# NP_5x5_2020.net
KiCad netlist of a schematic drawn in EAGLE
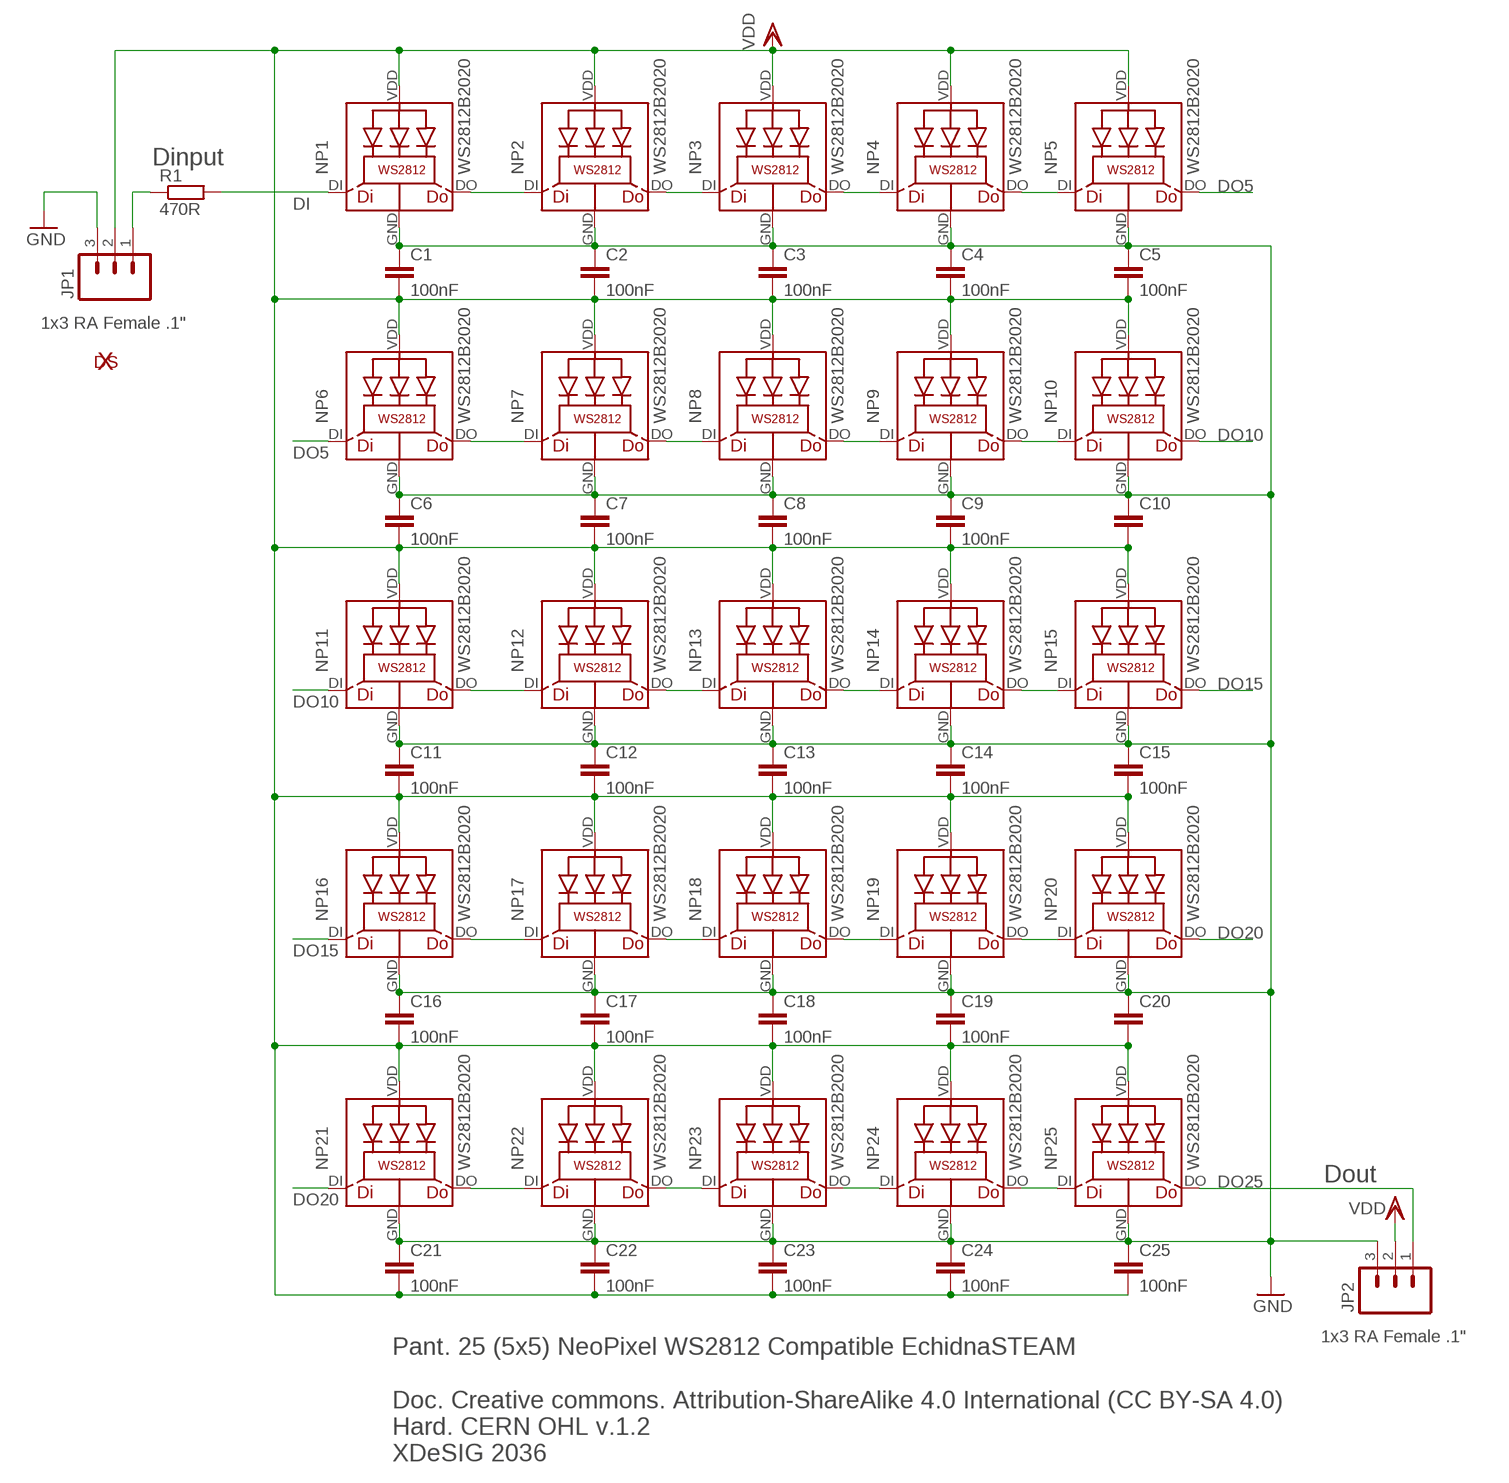
[diagram p0: schematic, sheet 1]

(export (version "E")
  (design (tool "Eeschema 10.0.6"))
  (components
    (comp (ref "C1")
      (value "100nF")
      (footprint "eagle-import:C0402")
      (libsource (lib "eagle-import") (part "C-EUC0402"))
    )
    (comp (ref "C2")
      (value "100nF")
      (footprint "eagle-import:C0402")
      (libsource (lib "eagle-import") (part "C-EUC0402"))
    )
    (comp (ref "C3")
      (value "100nF")
      (footprint "eagle-import:C0402")
      (libsource (lib "eagle-import") (part "C-EUC0402"))
    )
    (comp (ref "C4")
      (value "100nF")
      (footprint "eagle-import:C0402")
      (libsource (lib "eagle-import") (part "C-EUC0402"))
    )
    (comp (ref "C5")
      (value "100nF")
      (footprint "eagle-import:C0402")
      (libsource (lib "eagle-import") (part "C-EUC0402"))
    )
    (comp (ref "C6")
      (value "100nF")
      (footprint "eagle-import:C0402")
      (libsource (lib "eagle-import") (part "C-EUC0402"))
    )
    (comp (ref "C7")
      (value "100nF")
      (footprint "eagle-import:C0402")
      (libsource (lib "eagle-import") (part "C-EUC0402"))
    )
    (comp (ref "C8")
      (value "100nF")
      (footprint "eagle-import:C0402")
      (libsource (lib "eagle-import") (part "C-EUC0402"))
    )
    (comp (ref "C9")
      (value "100nF")
      (footprint "eagle-import:C0402")
      (libsource (lib "eagle-import") (part "C-EUC0402"))
    )
    (comp (ref "C10")
      (value "C-EUC0402")
      (footprint "eagle-import:C0402")
      (libsource (lib "eagle-import") (part "C-EUC0402"))
    )
    (comp (ref "C11")
      (value "100nF")
      (footprint "eagle-import:C0402")
      (libsource (lib "eagle-import") (part "C-EUC0402"))
    )
    (comp (ref "C12")
      (value "100nF")
      (footprint "eagle-import:C0402")
      (libsource (lib "eagle-import") (part "C-EUC0402"))
    )
    (comp (ref "C13")
      (value "100nF")
      (footprint "eagle-import:C0402")
      (libsource (lib "eagle-import") (part "C-EUC0402"))
    )
    (comp (ref "C14")
      (value "100nF")
      (footprint "eagle-import:C0402")
      (libsource (lib "eagle-import") (part "C-EUC0402"))
    )
    (comp (ref "C15")
      (value "100nF")
      (footprint "eagle-import:C0402")
      (libsource (lib "eagle-import") (part "C-EUC0402"))
    )
    (comp (ref "C16")
      (value "100nF")
      (footprint "eagle-import:C0402")
      (libsource (lib "eagle-import") (part "C-EUC0402"))
    )
    (comp (ref "C17")
      (value "100nF")
      (footprint "eagle-import:C0402")
      (libsource (lib "eagle-import") (part "C-EUC0402"))
    )
    (comp (ref "C18")
      (value "100nF")
      (footprint "eagle-import:C0402")
      (libsource (lib "eagle-import") (part "C-EUC0402"))
    )
    (comp (ref "C19")
      (value "100nF")
      (footprint "eagle-import:C0402")
      (libsource (lib "eagle-import") (part "C-EUC0402"))
    )
    (comp (ref "C20")
      (value "C-EUC0402")
      (footprint "eagle-import:C0402")
      (libsource (lib "eagle-import") (part "C-EUC0402"))
    )
    (comp (ref "C21")
      (value "100nF")
      (footprint "eagle-import:C0402")
      (libsource (lib "eagle-import") (part "C-EUC0402"))
    )
    (comp (ref "C22")
      (value "100nF")
      (footprint "eagle-import:C0402")
      (libsource (lib "eagle-import") (part "C-EUC0402"))
    )
    (comp (ref "C23")
      (value "100nF")
      (footprint "eagle-import:C0402")
      (libsource (lib "eagle-import") (part "C-EUC0402"))
    )
    (comp (ref "C24")
      (value "100nF")
      (footprint "eagle-import:C0402")
      (libsource (lib "eagle-import") (part "C-EUC0402"))
    )
    (comp (ref "C25")
      (value "100nF")
      (footprint "eagle-import:C0402")
      (libsource (lib "eagle-import") (part "C-EUC0402"))
    )
    (comp (ref "JP1")
      (value "1x3 RA Female .1\"")
      (footprint "eagle-import:1X03_SMD_RA_FEMALE")
      (libsource (lib "eagle-import") (part "M03SMD_RA_FEMALE"))
    )
    (comp (ref "JP2")
      (value "1x3 RA Female .1\"")
      (footprint "eagle-import:1X03_SMD_RA_FEMALE")
      (libsource (lib "eagle-import") (part "M03SMD_RA_FEMALE"))
    )
    (comp (ref "NP1")
      (value "WS2812B2020")
      (footprint "eagle-import:2020")
      (libsource (lib "eagle-import") (part "WS2812B2020"))
    )
    (comp (ref "NP2")
      (value "WS2812B2020")
      (footprint "eagle-import:2020")
      (libsource (lib "eagle-import") (part "WS2812B2020"))
    )
    (comp (ref "NP3")
      (value "WS2812B2020")
      (footprint "eagle-import:2020")
      (libsource (lib "eagle-import") (part "WS2812B2020"))
    )
    (comp (ref "NP4")
      (value "WS2812B2020")
      (footprint "eagle-import:2020")
      (libsource (lib "eagle-import") (part "WS2812B2020"))
    )
    (comp (ref "NP5")
      (value "WS2812B2020")
      (footprint "eagle-import:2020")
      (libsource (lib "eagle-import") (part "WS2812B2020"))
    )
    (comp (ref "NP6")
      (value "WS2812B2020")
      (footprint "eagle-import:2020")
      (libsource (lib "eagle-import") (part "WS2812B2020"))
    )
    (comp (ref "NP7")
      (value "WS2812B2020")
      (footprint "eagle-import:2020")
      (libsource (lib "eagle-import") (part "WS2812B2020"))
    )
    (comp (ref "NP8")
      (value "WS2812B2020")
      (footprint "eagle-import:2020")
      (libsource (lib "eagle-import") (part "WS2812B2020"))
    )
    (comp (ref "NP9")
      (value "WS2812B2020")
      (footprint "eagle-import:2020")
      (libsource (lib "eagle-import") (part "WS2812B2020"))
    )
    (comp (ref "NP10")
      (value "WS2812B2020")
      (footprint "eagle-import:2020")
      (libsource (lib "eagle-import") (part "WS2812B2020"))
    )
    (comp (ref "NP11")
      (value "WS2812B2020")
      (footprint "eagle-import:2020")
      (libsource (lib "eagle-import") (part "WS2812B2020"))
    )
    (comp (ref "NP12")
      (value "WS2812B2020")
      (footprint "eagle-import:2020")
      (libsource (lib "eagle-import") (part "WS2812B2020"))
    )
    (comp (ref "NP13")
      (value "WS2812B2020")
      (footprint "eagle-import:2020")
      (libsource (lib "eagle-import") (part "WS2812B2020"))
    )
    (comp (ref "NP14")
      (value "WS2812B2020")
      (footprint "eagle-import:2020")
      (libsource (lib "eagle-import") (part "WS2812B2020"))
    )
    (comp (ref "NP15")
      (value "WS2812B2020")
      (footprint "eagle-import:2020")
      (libsource (lib "eagle-import") (part "WS2812B2020"))
    )
    (comp (ref "NP16")
      (value "WS2812B2020")
      (footprint "eagle-import:2020")
      (libsource (lib "eagle-import") (part "WS2812B2020"))
    )
    (comp (ref "NP17")
      (value "WS2812B2020")
      (footprint "eagle-import:2020")
      (libsource (lib "eagle-import") (part "WS2812B2020"))
    )
    (comp (ref "NP18")
      (value "WS2812B2020")
      (footprint "eagle-import:2020")
      (libsource (lib "eagle-import") (part "WS2812B2020"))
    )
    (comp (ref "NP19")
      (value "WS2812B2020")
      (footprint "eagle-import:2020")
      (libsource (lib "eagle-import") (part "WS2812B2020"))
    )
    (comp (ref "NP20")
      (value "WS2812B2020")
      (footprint "eagle-import:2020")
      (libsource (lib "eagle-import") (part "WS2812B2020"))
    )
    (comp (ref "NP21")
      (value "WS2812B2020")
      (footprint "eagle-import:2020")
      (libsource (lib "eagle-import") (part "WS2812B2020"))
    )
    (comp (ref "NP22")
      (value "WS2812B2020")
      (footprint "eagle-import:2020")
      (libsource (lib "eagle-import") (part "WS2812B2020"))
    )
    (comp (ref "NP23")
      (value "WS2812B2020")
      (footprint "eagle-import:2020")
      (libsource (lib "eagle-import") (part "WS2812B2020"))
    )
    (comp (ref "NP24")
      (value "WS2812B2020")
      (footprint "eagle-import:2020")
      (libsource (lib "eagle-import") (part "WS2812B2020"))
    )
    (comp (ref "NP25")
      (value "WS2812B2020")
      (footprint "eagle-import:2020")
      (libsource (lib "eagle-import") (part "WS2812B2020"))
    )
    (comp (ref "R1")
      (value "470R")
      (footprint "eagle-import:R0603")
      (libsource (lib "eagle-import") (part "R-EU_R0603"))
    )
    (comp (ref "U$1")
      (value "XDESIG_XDESIG5MM")
      (footprint "eagle-import:XDESIG_XDESIG_CU")
      (libsource (lib "eagle-import") (part "XDESIG_XDESIG5MM"))
    )
  )
  (nets
    (net (code "1") (name "/DI") (class "Default")
      (node (ref "NP1") (pin "DI") (pinfunction "DI_DI") (pintype "input"))
      (node (ref "R1") (pin "2") (pinfunction "2_2") (pintype "passive"))
    )
    (net (code "2") (name "/DO5") (class "Default")
      (node (ref "NP5") (pin "DO") (pinfunction "DO_DO") (pintype "output"))
      (node (ref "NP6") (pin "DI") (pinfunction "DI_DI") (pintype "input"))
    )
    (net (code "3") (name "/DO10") (class "Default")
      (node (ref "NP10") (pin "DO") (pinfunction "DO_DO") (pintype "output"))
      (node (ref "NP11") (pin "DI") (pinfunction "DI_DI") (pintype "input"))
    )
    (net (code "4") (name "/DO15") (class "Default")
      (node (ref "NP15") (pin "DO") (pinfunction "DO_DO") (pintype "output"))
      (node (ref "NP16") (pin "DI") (pinfunction "DI_DI") (pintype "input"))
    )
    (net (code "5") (name "/DO20") (class "Default")
      (node (ref "NP20") (pin "DO") (pinfunction "DO_DO") (pintype "output"))
      (node (ref "NP21") (pin "DI") (pinfunction "DI_DI") (pintype "input"))
    )
    (net (code "6") (name "/DO25") (class "Default")
      (node (ref "JP2") (pin "1") (pinfunction "1_1") (pintype "passive"))
      (node (ref "NP25") (pin "DO") (pinfunction "DO_DO") (pintype "output"))
    )
    (net (code "7") (name "GND") (class "Default")
      (node (ref "C1") (pin "1") (pinfunction "1_1") (pintype "passive"))
      (node (ref "C10") (pin "1") (pinfunction "1_1") (pintype "passive"))
      (node (ref "C11") (pin "1") (pinfunction "1_1") (pintype "passive"))
      (node (ref "C12") (pin "1") (pinfunction "1_1") (pintype "passive"))
      (node (ref "C13") (pin "1") (pinfunction "1_1") (pintype "passive"))
      (node (ref "C14") (pin "1") (pinfunction "1_1") (pintype "passive"))
      (node (ref "C15") (pin "1") (pinfunction "1_1") (pintype "passive"))
      (node (ref "C16") (pin "1") (pinfunction "1_1") (pintype "passive"))
      (node (ref "C17") (pin "1") (pinfunction "1_1") (pintype "passive"))
      (node (ref "C18") (pin "1") (pinfunction "1_1") (pintype "passive"))
      (node (ref "C19") (pin "1") (pinfunction "1_1") (pintype "passive"))
      (node (ref "C2") (pin "1") (pinfunction "1_1") (pintype "passive"))
      (node (ref "C20") (pin "1") (pinfunction "1_1") (pintype "passive"))
      (node (ref "C21") (pin "1") (pinfunction "1_1") (pintype "passive"))
      (node (ref "C22") (pin "1") (pinfunction "1_1") (pintype "passive"))
      (node (ref "C23") (pin "1") (pinfunction "1_1") (pintype "passive"))
      (node (ref "C24") (pin "1") (pinfunction "1_1") (pintype "passive"))
      (node (ref "C25") (pin "1") (pinfunction "1_1") (pintype "passive"))
      (node (ref "C3") (pin "1") (pinfunction "1_1") (pintype "passive"))
      (node (ref "C4") (pin "1") (pinfunction "1_1") (pintype "passive"))
      (node (ref "C5") (pin "1") (pinfunction "1_1") (pintype "passive"))
      (node (ref "C6") (pin "1") (pinfunction "1_1") (pintype "passive"))
      (node (ref "C7") (pin "1") (pinfunction "1_1") (pintype "passive"))
      (node (ref "C8") (pin "1") (pinfunction "1_1") (pintype "passive"))
      (node (ref "C9") (pin "1") (pinfunction "1_1") (pintype "passive"))
      (node (ref "JP1") (pin "3") (pinfunction "3_3") (pintype "passive"))
      (node (ref "JP2") (pin "3") (pinfunction "3_3") (pintype "passive"))
      (node (ref "NP1") (pin "GND") (pinfunction "GND_GND") (pintype "power_in"))
      (node (ref "NP10") (pin "GND") (pinfunction "GND_GND") (pintype "power_in"))
      (node (ref "NP11") (pin "GND") (pinfunction "GND_GND") (pintype "power_in"))
      (node (ref "NP12") (pin "GND") (pinfunction "GND_GND") (pintype "power_in"))
      (node (ref "NP13") (pin "GND") (pinfunction "GND_GND") (pintype "power_in"))
      (node (ref "NP14") (pin "GND") (pinfunction "GND_GND") (pintype "power_in"))
      (node (ref "NP15") (pin "GND") (pinfunction "GND_GND") (pintype "power_in"))
      (node (ref "NP16") (pin "GND") (pinfunction "GND_GND") (pintype "power_in"))
      (node (ref "NP17") (pin "GND") (pinfunction "GND_GND") (pintype "power_in"))
      (node (ref "NP18") (pin "GND") (pinfunction "GND_GND") (pintype "power_in"))
      (node (ref "NP19") (pin "GND") (pinfunction "GND_GND") (pintype "power_in"))
      (node (ref "NP2") (pin "GND") (pinfunction "GND_GND") (pintype "power_in"))
      (node (ref "NP20") (pin "GND") (pinfunction "GND_GND") (pintype "power_in"))
      (node (ref "NP21") (pin "GND") (pinfunction "GND_GND") (pintype "power_in"))
      (node (ref "NP22") (pin "GND") (pinfunction "GND_GND") (pintype "power_in"))
      (node (ref "NP23") (pin "GND") (pinfunction "GND_GND") (pintype "power_in"))
      (node (ref "NP24") (pin "GND") (pinfunction "GND_GND") (pintype "power_in"))
      (node (ref "NP25") (pin "GND") (pinfunction "GND_GND") (pintype "power_in"))
      (node (ref "NP3") (pin "GND") (pinfunction "GND_GND") (pintype "power_in"))
      (node (ref "NP4") (pin "GND") (pinfunction "GND_GND") (pintype "power_in"))
      (node (ref "NP5") (pin "GND") (pinfunction "GND_GND") (pintype "power_in"))
      (node (ref "NP6") (pin "GND") (pinfunction "GND_GND") (pintype "power_in"))
      (node (ref "NP7") (pin "GND") (pinfunction "GND_GND") (pintype "power_in"))
      (node (ref "NP8") (pin "GND") (pinfunction "GND_GND") (pintype "power_in"))
      (node (ref "NP9") (pin "GND") (pinfunction "GND_GND") (pintype "power_in"))
    )
    (net (code "8") (name "Net-(JP1-Pad1)") (class "Default")
      (node (ref "JP1") (pin "1") (pinfunction "1_1") (pintype "passive"))
      (node (ref "R1") (pin "1") (pinfunction "1_1") (pintype "passive"))
    )
    (net (code "9") (name "Net-(NP1-PadDO)") (class "Default")
      (node (ref "NP1") (pin "DO") (pinfunction "DO_DO") (pintype "output"))
      (node (ref "NP2") (pin "DI") (pinfunction "DI_DI") (pintype "input"))
    )
    (net (code "10") (name "Net-(NP2-PadDO)") (class "Default")
      (node (ref "NP2") (pin "DO") (pinfunction "DO_DO") (pintype "output"))
      (node (ref "NP3") (pin "DI") (pinfunction "DI_DI") (pintype "input"))
    )
    (net (code "11") (name "Net-(NP3-PadDO)") (class "Default")
      (node (ref "NP3") (pin "DO") (pinfunction "DO_DO") (pintype "output"))
      (node (ref "NP4") (pin "DI") (pinfunction "DI_DI") (pintype "input"))
    )
    (net (code "12") (name "Net-(NP4-PadDO)") (class "Default")
      (node (ref "NP4") (pin "DO") (pinfunction "DO_DO") (pintype "output"))
      (node (ref "NP5") (pin "DI") (pinfunction "DI_DI") (pintype "input"))
    )
    (net (code "13") (name "Net-(NP6-PadDO)") (class "Default")
      (node (ref "NP6") (pin "DO") (pinfunction "DO_DO") (pintype "output"))
      (node (ref "NP7") (pin "DI") (pinfunction "DI_DI") (pintype "input"))
    )
    (net (code "14") (name "Net-(NP7-PadDO)") (class "Default")
      (node (ref "NP7") (pin "DO") (pinfunction "DO_DO") (pintype "output"))
      (node (ref "NP8") (pin "DI") (pinfunction "DI_DI") (pintype "input"))
    )
    (net (code "15") (name "Net-(NP8-PadDO)") (class "Default")
      (node (ref "NP8") (pin "DO") (pinfunction "DO_DO") (pintype "output"))
      (node (ref "NP9") (pin "DI") (pinfunction "DI_DI") (pintype "input"))
    )
    (net (code "16") (name "Net-(NP10-PadDI)") (class "Default")
      (node (ref "NP10") (pin "DI") (pinfunction "DI_DI") (pintype "input"))
      (node (ref "NP9") (pin "DO") (pinfunction "DO_DO") (pintype "output"))
    )
    (net (code "17") (name "Net-(NP11-PadDO)") (class "Default")
      (node (ref "NP11") (pin "DO") (pinfunction "DO_DO") (pintype "output"))
      (node (ref "NP12") (pin "DI") (pinfunction "DI_DI") (pintype "input"))
    )
    (net (code "18") (name "Net-(NP12-PadDO)") (class "Default")
      (node (ref "NP12") (pin "DO") (pinfunction "DO_DO") (pintype "output"))
      (node (ref "NP13") (pin "DI") (pinfunction "DI_DI") (pintype "input"))
    )
    (net (code "19") (name "Net-(NP13-PadDO)") (class "Default")
      (node (ref "NP13") (pin "DO") (pinfunction "DO_DO") (pintype "output"))
      (node (ref "NP14") (pin "DI") (pinfunction "DI_DI") (pintype "input"))
    )
    (net (code "20") (name "Net-(NP14-PadDO)") (class "Default")
      (node (ref "NP14") (pin "DO") (pinfunction "DO_DO") (pintype "output"))
      (node (ref "NP15") (pin "DI") (pinfunction "DI_DI") (pintype "input"))
    )
    (net (code "21") (name "Net-(NP16-PadDO)") (class "Default")
      (node (ref "NP16") (pin "DO") (pinfunction "DO_DO") (pintype "output"))
      (node (ref "NP17") (pin "DI") (pinfunction "DI_DI") (pintype "input"))
    )
    (net (code "22") (name "Net-(NP17-PadDO)") (class "Default")
      (node (ref "NP17") (pin "DO") (pinfunction "DO_DO") (pintype "output"))
      (node (ref "NP18") (pin "DI") (pinfunction "DI_DI") (pintype "input"))
    )
    (net (code "23") (name "Net-(NP18-PadDO)") (class "Default")
      (node (ref "NP18") (pin "DO") (pinfunction "DO_DO") (pintype "output"))
      (node (ref "NP19") (pin "DI") (pinfunction "DI_DI") (pintype "input"))
    )
    (net (code "24") (name "Net-(NP19-PadDO)") (class "Default")
      (node (ref "NP19") (pin "DO") (pinfunction "DO_DO") (pintype "output"))
      (node (ref "NP20") (pin "DI") (pinfunction "DI_DI") (pintype "input"))
    )
    (net (code "25") (name "Net-(NP21-PadDO)") (class "Default")
      (node (ref "NP21") (pin "DO") (pinfunction "DO_DO") (pintype "output"))
      (node (ref "NP22") (pin "DI") (pinfunction "DI_DI") (pintype "input"))
    )
    (net (code "26") (name "Net-(NP22-PadDO)") (class "Default")
      (node (ref "NP22") (pin "DO") (pinfunction "DO_DO") (pintype "output"))
      (node (ref "NP23") (pin "DI") (pinfunction "DI_DI") (pintype "input"))
    )
    (net (code "27") (name "Net-(NP23-PadDO)") (class "Default")
      (node (ref "NP23") (pin "DO") (pinfunction "DO_DO") (pintype "output"))
      (node (ref "NP24") (pin "DI") (pinfunction "DI_DI") (pintype "input"))
    )
    (net (code "28") (name "Net-(NP24-PadDO)") (class "Default")
      (node (ref "NP24") (pin "DO") (pinfunction "DO_DO") (pintype "output"))
      (node (ref "NP25") (pin "DI") (pinfunction "DI_DI") (pintype "input"))
    )
    (net (code "29") (name "VDD") (class "Default")
      (node (ref "C1") (pin "2") (pinfunction "2_2") (pintype "passive"))
      (node (ref "C10") (pin "2") (pinfunction "2_2") (pintype "passive"))
      (node (ref "C11") (pin "2") (pinfunction "2_2") (pintype "passive"))
      (node (ref "C12") (pin "2") (pinfunction "2_2") (pintype "passive"))
      (node (ref "C13") (pin "2") (pinfunction "2_2") (pintype "passive"))
      (node (ref "C14") (pin "2") (pinfunction "2_2") (pintype "passive"))
      (node (ref "C15") (pin "2") (pinfunction "2_2") (pintype "passive"))
      (node (ref "C16") (pin "2") (pinfunction "2_2") (pintype "passive"))
      (node (ref "C17") (pin "2") (pinfunction "2_2") (pintype "passive"))
      (node (ref "C18") (pin "2") (pinfunction "2_2") (pintype "passive"))
      (node (ref "C19") (pin "2") (pinfunction "2_2") (pintype "passive"))
      (node (ref "C2") (pin "2") (pinfunction "2_2") (pintype "passive"))
      (node (ref "C20") (pin "2") (pinfunction "2_2") (pintype "passive"))
      (node (ref "C21") (pin "2") (pinfunction "2_2") (pintype "passive"))
      (node (ref "C22") (pin "2") (pinfunction "2_2") (pintype "passive"))
      (node (ref "C23") (pin "2") (pinfunction "2_2") (pintype "passive"))
      (node (ref "C24") (pin "2") (pinfunction "2_2") (pintype "passive"))
      (node (ref "C25") (pin "2") (pinfunction "2_2") (pintype "passive"))
      (node (ref "C3") (pin "2") (pinfunction "2_2") (pintype "passive"))
      (node (ref "C4") (pin "2") (pinfunction "2_2") (pintype "passive"))
      (node (ref "C5") (pin "2") (pinfunction "2_2") (pintype "passive"))
      (node (ref "C6") (pin "2") (pinfunction "2_2") (pintype "passive"))
      (node (ref "C7") (pin "2") (pinfunction "2_2") (pintype "passive"))
      (node (ref "C8") (pin "2") (pinfunction "2_2") (pintype "passive"))
      (node (ref "C9") (pin "2") (pinfunction "2_2") (pintype "passive"))
      (node (ref "JP1") (pin "2") (pinfunction "2_2") (pintype "passive"))
      (node (ref "JP2") (pin "2") (pinfunction "2_2") (pintype "passive"))
      (node (ref "NP1") (pin "VDD") (pinfunction "LEDVDD_VDD") (pintype "power_in"))
      (node (ref "NP10") (pin "VDD") (pinfunction "LEDVDD_VDD") (pintype "power_in"))
      (node (ref "NP11") (pin "VDD") (pinfunction "LEDVDD_VDD") (pintype "power_in"))
      (node (ref "NP12") (pin "VDD") (pinfunction "LEDVDD_VDD") (pintype "power_in"))
      (node (ref "NP13") (pin "VDD") (pinfunction "LEDVDD_VDD") (pintype "power_in"))
      (node (ref "NP14") (pin "VDD") (pinfunction "LEDVDD_VDD") (pintype "power_in"))
      (node (ref "NP15") (pin "VDD") (pinfunction "LEDVDD_VDD") (pintype "power_in"))
      (node (ref "NP16") (pin "VDD") (pinfunction "LEDVDD_VDD") (pintype "power_in"))
      (node (ref "NP17") (pin "VDD") (pinfunction "LEDVDD_VDD") (pintype "power_in"))
      (node (ref "NP18") (pin "VDD") (pinfunction "LEDVDD_VDD") (pintype "power_in"))
      (node (ref "NP19") (pin "VDD") (pinfunction "LEDVDD_VDD") (pintype "power_in"))
      (node (ref "NP2") (pin "VDD") (pinfunction "LEDVDD_VDD") (pintype "power_in"))
      (node (ref "NP20") (pin "VDD") (pinfunction "LEDVDD_VDD") (pintype "power_in"))
      (node (ref "NP21") (pin "VDD") (pinfunction "LEDVDD_VDD") (pintype "power_in"))
      (node (ref "NP22") (pin "VDD") (pinfunction "LEDVDD_VDD") (pintype "power_in"))
      (node (ref "NP23") (pin "VDD") (pinfunction "LEDVDD_VDD") (pintype "power_in"))
      (node (ref "NP24") (pin "VDD") (pinfunction "LEDVDD_VDD") (pintype "power_in"))
      (node (ref "NP25") (pin "VDD") (pinfunction "LEDVDD_VDD") (pintype "power_in"))
      (node (ref "NP3") (pin "VDD") (pinfunction "LEDVDD_VDD") (pintype "power_in"))
      (node (ref "NP4") (pin "VDD") (pinfunction "LEDVDD_VDD") (pintype "power_in"))
      (node (ref "NP5") (pin "VDD") (pinfunction "LEDVDD_VDD") (pintype "power_in"))
      (node (ref "NP6") (pin "VDD") (pinfunction "LEDVDD_VDD") (pintype "power_in"))
      (node (ref "NP7") (pin "VDD") (pinfunction "LEDVDD_VDD") (pintype "power_in"))
      (node (ref "NP8") (pin "VDD") (pinfunction "LEDVDD_VDD") (pintype "power_in"))
      (node (ref "NP9") (pin "VDD") (pinfunction "LEDVDD_VDD") (pintype "power_in"))
    )
  )
)
